# Buttons.net
KiCad netlist of a schematic drawn in Altium Designer
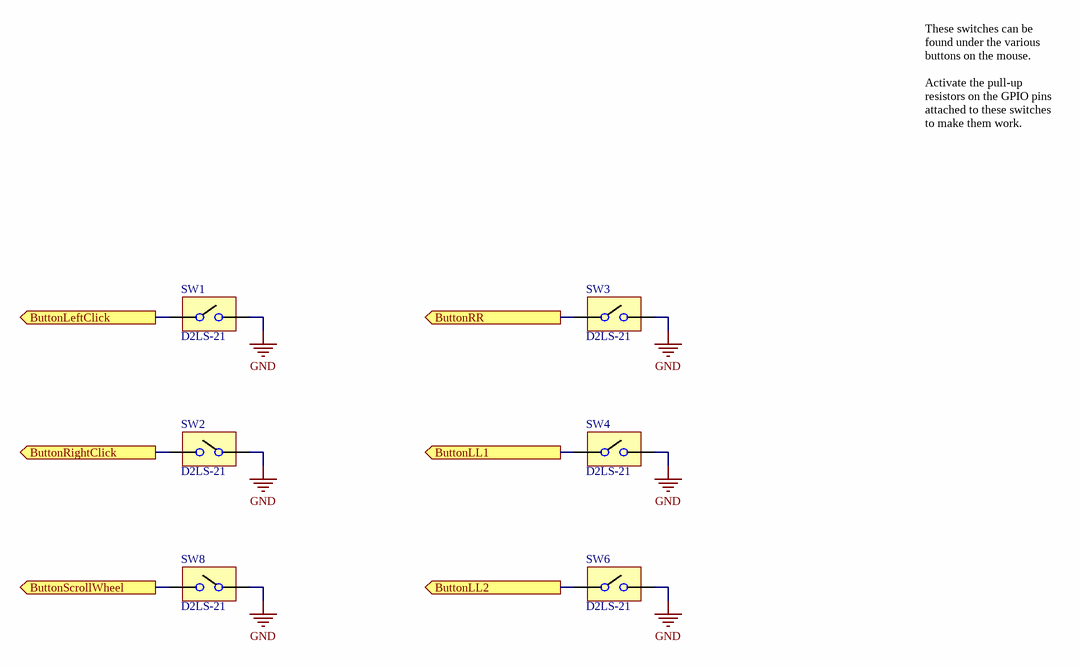
[diagram p0: Buttons.SchDoc]

(export (version "E")
  (design (tool "Eeschema 10.0.6"))
  (components
    (comp (ref "SW1")
      (value "D2LS-21")
      (footprint "D2LS-21")
      (description "Compact Surface-mounting Switch for long durability")
      (libsource (lib "Switches") (part "D2LS-21"))
    )
    (comp (ref "SW2")
      (value "D2LS-21")
      (footprint "D2LS-21")
      (description "Compact Surface-mounting Switch for long durability")
      (libsource (lib "") (part "D2LS-21_1"))
    )
    (comp (ref "SW3")
      (value "D2LS-21")
      (footprint "D2LS-21")
      (description "Compact Surface-mounting Switch for long durability")
      (libsource (lib "Switches") (part "D2LS-21"))
    )
    (comp (ref "SW4")
      (value "D2LS-21")
      (footprint "D2LS-21")
      (description "Compact Surface-mounting Switch for long durability")
      (libsource (lib "Switches") (part "D2LS-21"))
    )
    (comp (ref "SW6")
      (value "D2LS-21")
      (footprint "D2LS-21")
      (description "Compact Surface-mounting Switch for long durability")
      (libsource (lib "Switches") (part "D2LS-21"))
    )
    (comp (ref "SW8")
      (value "D2LS-21")
      (footprint "D2LS-21")
      (description "Compact Surface-mounting Switch for long durability")
      (libsource (lib "") (part "D2LS-21_1"))
    )
  )
  (nets
    (net (code "1") (name "/ButtonLL1") (class "Default")
      (node (ref "SW4") (pin "A") (pinfunction "A_A") (pintype "passive"))
    )
    (net (code "2") (name "/ButtonLL2") (class "Default")
      (node (ref "SW6") (pin "A") (pinfunction "A_A") (pintype "passive"))
    )
    (net (code "3") (name "/ButtonLeftClick") (class "Default")
      (node (ref "SW1") (pin "A") (pinfunction "A_A") (pintype "passive"))
    )
    (net (code "4") (name "/ButtonRR") (class "Default")
      (node (ref "SW3") (pin "A") (pinfunction "A_A") (pintype "passive"))
    )
    (net (code "5") (name "/ButtonRightClick") (class "Default")
      (node (ref "SW2") (pin "B") (pinfunction "B_B") (pintype "passive"))
    )
    (net (code "6") (name "/ButtonScrollWheel") (class "Default")
      (node (ref "SW8") (pin "B") (pinfunction "B_B") (pintype "passive"))
    )
    (net (code "7") (name "GND") (class "Default")
      (node (ref "SW1") (pin "B") (pinfunction "B_B") (pintype "passive"))
      (node (ref "SW2") (pin "A") (pinfunction "A_A") (pintype "passive"))
      (node (ref "SW3") (pin "B") (pinfunction "B_B") (pintype "passive"))
      (node (ref "SW4") (pin "B") (pinfunction "B_B") (pintype "passive"))
      (node (ref "SW6") (pin "B") (pinfunction "B_B") (pintype "passive"))
      (node (ref "SW8") (pin "A") (pinfunction "A_A") (pintype "passive"))
    )
  )
)
